# Attiny85_BT-Relay.net
KiCad netlist of a schematic drawn in EAGLE
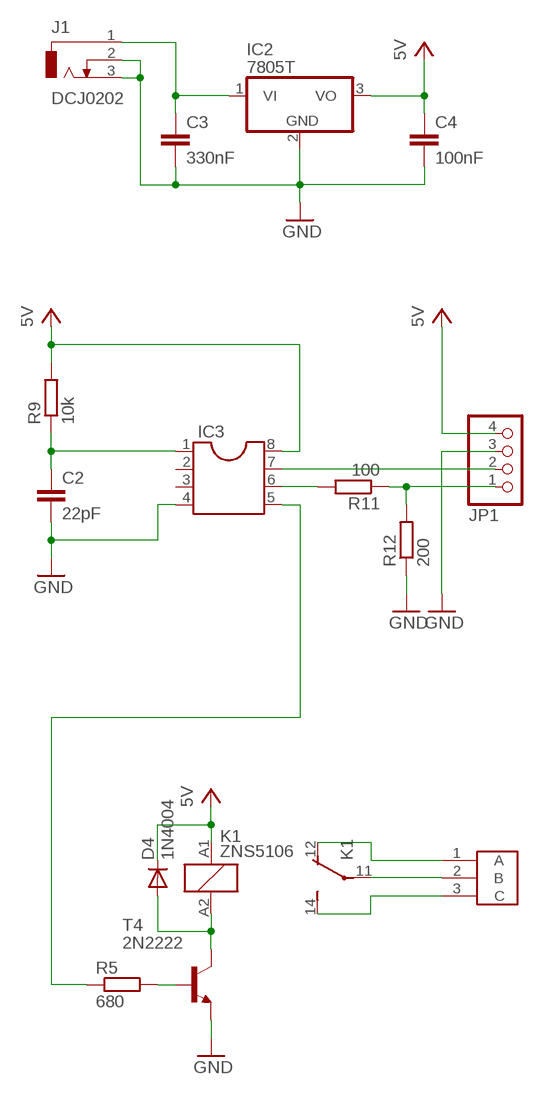
[diagram p0: schematic, sheet 1]

(export (version "E")
  (design (tool "Eeschema 10.0.6"))
  (components
    (comp (ref "C2")
      (value "22pF")
      (footprint "eagle-import:C050-025X075")
      (libsource (lib "eagle-import") (part "C-EU050-025X075"))
    )
    (comp (ref "C3")
      (value "330nF")
      (footprint "eagle-import:C050-025X075")
      (libsource (lib "eagle-import") (part "C-EU050-025X075"))
    )
    (comp (ref "C4")
      (value "100nF")
      (footprint "eagle-import:C050-025X075")
      (libsource (lib "eagle-import") (part "C-EU050-025X075"))
    )
    (comp (ref "D4")
      (value "1N4004")
      (footprint "eagle-import:DO41-10")
      (libsource (lib "eagle-import") (part "1N4004"))
    )
    (comp (ref "IC2")
      (value "7805T")
      (footprint "eagle-import:TO220H")
      (libsource (lib "eagle-import") (part "78T05"))
    )
    (comp (ref "IC3")
      (value "DIL8S")
      (footprint "eagle-import:SOCKET-08")
      (libsource (lib "eagle-import") (part "DIL8S"))
    )
    (comp (ref "J1")
      (value "DCJ0202")
      (footprint "eagle-import:DCJ0202")
      (libsource (lib "eagle-import") (part "DCJ0202"))
    )
    (comp (ref "JP1")
      (value "PINHD-1X4")
      (footprint "eagle-import:1X04")
      (libsource (lib "eagle-import") (part "PINHD-1X4"))
    )
    (comp (ref "K1")
      (value "ZNS5106")
      (footprint "eagle-import:ZN5")
      (libsource (lib "eagle-import") (part "ZNS5106"))
    )
    (comp (ref "R5")
      (value "680")
      (footprint "eagle-import:0204_7")
      (libsource (lib "eagle-import") (part "R-EU_0204/7"))
    )
    (comp (ref "R9")
      (value "10k")
      (footprint "eagle-import:0204_7")
      (libsource (lib "eagle-import") (part "R-EU_0204/7"))
    )
    (comp (ref "R11")
      (value "100")
      (footprint "eagle-import:0204_7")
      (libsource (lib "eagle-import") (part "R-EU_0204/7"))
    )
    (comp (ref "R12")
      (value "200")
      (footprint "eagle-import:0204_7")
      (libsource (lib "eagle-import") (part "R-EU_0204/7"))
    )
    (comp (ref "T4")
      (value "2N2222")
      (footprint "eagle-import:TO18")
      (libsource (lib "eagle-import") (part "2N2222"))
    )
    (comp (ref "U$1")
      (value "POT_CONNECTOR")
      (footprint "eagle-import:POT_CONNECTOR")
      (libsource (lib "eagle-import") (part "POT_CONNECTOR"))
    )
  )
  (nets
    (net (code "1") (name "5V") (class "Default")
      (node (ref "C4") (pin "1") (pinfunction "1_1") (pintype "passive"))
      (node (ref "D4") (pin "C") (pinfunction "C_C") (pintype "passive"))
      (node (ref "IC2") (pin "3") (pinfunction "VO_3") (pintype "passive"))
      (node (ref "IC3") (pin "8") (pinfunction "8_8") (pintype "passive"))
      (node (ref "JP1") (pin "4") (pinfunction "4_4") (pintype "passive"))
      (node (ref "K1") (pin "A1") (pinfunction "1_A1") (pintype "passive"))
      (node (ref "R9") (pin "2") (pinfunction "2_2") (pintype "passive"))
    )
    (net (code "2") (name "GND") (class "Default")
      (node (ref "C2") (pin "2") (pinfunction "2_2") (pintype "passive"))
      (node (ref "C3") (pin "2") (pinfunction "2_2") (pintype "passive"))
      (node (ref "C4") (pin "2") (pinfunction "2_2") (pintype "passive"))
      (node (ref "IC2") (pin "2") (pinfunction "GND_2") (pintype "passive"))
      (node (ref "IC3") (pin "4") (pinfunction "4_4") (pintype "passive"))
      (node (ref "J1") (pin "2") (pinfunction "2_2") (pintype "passive"))
      (node (ref "J1") (pin "3") (pinfunction "3_3") (pintype "passive"))
      (node (ref "JP1") (pin "3") (pinfunction "3_3") (pintype "passive"))
      (node (ref "R12") (pin "1") (pinfunction "1_1") (pintype "passive"))
      (node (ref "T4") (pin "1") (pinfunction "E_1") (pintype "passive"))
    )
    (net (code "3") (name "Net-(C2-Pad1)") (class "Default")
      (node (ref "C2") (pin "1") (pinfunction "1_1") (pintype "passive"))
      (node (ref "IC3") (pin "1") (pinfunction "1_1") (pintype "passive"))
      (node (ref "R9") (pin "1") (pinfunction "1_1") (pintype "passive"))
    )
    (net (code "4") (name "Net-(IC2-VI)") (class "Default")
      (node (ref "C3") (pin "1") (pinfunction "1_1") (pintype "passive"))
      (node (ref "IC2") (pin "1") (pinfunction "VI_1") (pintype "input"))
      (node (ref "J1") (pin "1") (pinfunction "1_1") (pintype "passive"))
    )
    (net (code "5") (name "Net-(IC3-Pad5)") (class "Default")
      (node (ref "IC3") (pin "5") (pinfunction "5_5") (pintype "passive"))
      (node (ref "R5") (pin "1") (pinfunction "1_1") (pintype "passive"))
    )
    (net (code "6") (name "Net-(IC3-Pad6)") (class "Default")
      (node (ref "IC3") (pin "6") (pinfunction "6_6") (pintype "passive"))
      (node (ref "R11") (pin "2") (pinfunction "2_2") (pintype "passive"))
    )
    (net (code "7") (name "Net-(IC3-Pad7)") (class "Default")
      (node (ref "IC3") (pin "7") (pinfunction "7_7") (pintype "passive"))
      (node (ref "JP1") (pin "2") (pinfunction "2_2") (pintype "passive"))
    )
    (net (code "8") (name "Net-(JP1-Pad1)") (class "Default")
      (node (ref "JP1") (pin "1") (pinfunction "1_1") (pintype "passive"))
      (node (ref "R11") (pin "1") (pinfunction "1_1") (pintype "passive"))
      (node (ref "R12") (pin "2") (pinfunction "2_2") (pintype "passive"))
    )
    (net (code "9") (name "Net-(K1A-2)") (class "Default")
      (node (ref "D4") (pin "A") (pinfunction "A_A") (pintype "passive"))
      (node (ref "K1") (pin "A2") (pinfunction "2_A2") (pintype "passive"))
      (node (ref "T4") (pin "3") (pinfunction "C_3") (pintype "passive"))
    )
    (net (code "10") (name "Net-(K1B-O)") (class "Default")
      (node (ref "K1") (pin "12") (pinfunction "O_12") (pintype "passive"))
      (node (ref "U$1") (pin "1") (pinfunction "A_1") (pintype "bidirectional"))
    )
    (net (code "11") (name "Net-(K1B-P)") (class "Default")
      (node (ref "K1") (pin "11") (pinfunction "P_11") (pintype "passive"))
      (node (ref "U$1") (pin "2") (pinfunction "B_2") (pintype "bidirectional"))
    )
    (net (code "12") (name "Net-(K1B-S)") (class "Default")
      (node (ref "K1") (pin "14") (pinfunction "S_14") (pintype "passive"))
      (node (ref "U$1") (pin "3") (pinfunction "C_3") (pintype "bidirectional"))
    )
    (net (code "13") (name "Net-(T4-B)") (class "Default")
      (node (ref "R5") (pin "2") (pinfunction "2_2") (pintype "passive"))
      (node (ref "T4") (pin "2") (pinfunction "B_2") (pintype "passive"))
    )
    (net (code "14") (name "unconnected-(IC3-Pad2)") (class "Default")
      (node (ref "IC3") (pin "2") (pinfunction "2_2") (pintype "passive"))
    )
    (net (code "15") (name "unconnected-(IC3-Pad3)") (class "Default")
      (node (ref "IC3") (pin "3") (pinfunction "3_3") (pintype "passive"))
    )
  )
)
